# SciQuest_NRF_Mesh.net
KiCad netlist of a schematic drawn in EAGLE
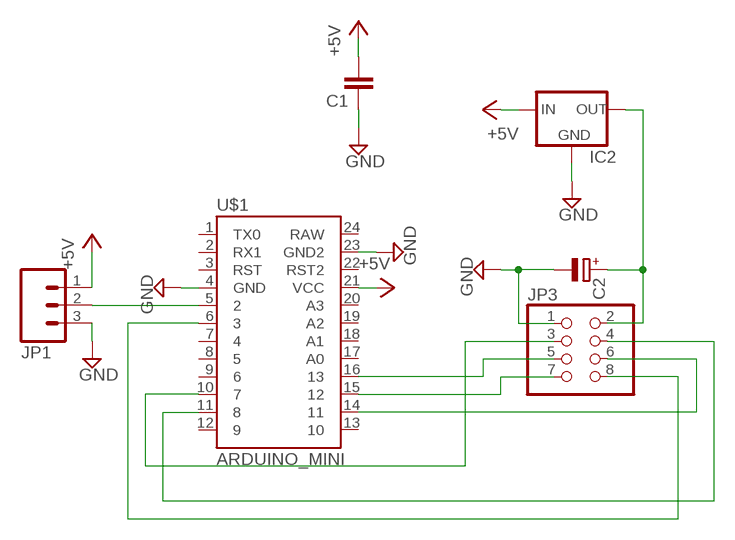
[diagram p0: schematic, sheet 1]

(export (version "E")
  (design (tool "Eeschema 10.0.6"))
  (components
    (comp (ref "C1")
      (value "C-EUC0805K")
      (footprint "eagle-import:C0805K")
      (libsource (lib "eagle-import") (part "C-EUC0805K"))
    )
    (comp (ref "C2")
      (value "CPOL-EUE2-4")
      (footprint "eagle-import:E2-4")
      (libsource (lib "eagle-import") (part "CPOL-EUE2-4"))
    )
    (comp (ref "IC2")
      (value "78LXX")
      (footprint "eagle-import:78LXX")
      (libsource (lib "eagle-import") (part "78LXX"))
    )
    (comp (ref "JP1")
      (value "M03LONGPADS")
      (footprint "eagle-import:1X03_LONGPADS")
      (libsource (lib "eagle-import") (part "M03LONGPADS"))
    )
    (comp (ref "JP3")
      (value "PINHD-2X4")
      (footprint "eagle-import:2X04")
      (libsource (lib "eagle-import") (part "PINHD-2X4"))
    )
    (comp (ref "U$1")
      (value "ARDUINO_MINI")
      (footprint "eagle-import:ARDUINO_MINI")
      (libsource (lib "eagle-import") (part "ARDUINO_MINI"))
    )
  )
  (nets
    (net (code "1") (name "+5V") (class "Default")
      (node (ref "C1") (pin "2") (pinfunction "2_2") (pintype "passive"))
      (node (ref "IC2") (pin "IN") (pinfunction "IN_IN") (pintype "input"))
      (node (ref "JP1") (pin "1") (pinfunction "1_1") (pintype "passive"))
      (node (ref "U$1") (pin "21") (pinfunction "VCC_21") (pintype "bidirectional"))
    )
    (net (code "2") (name "GND") (class "Default")
      (node (ref "C1") (pin "1") (pinfunction "1_1") (pintype "passive"))
      (node (ref "C2") (pin "-") (pinfunction "-_-") (pintype "passive"))
      (node (ref "IC2") (pin "GND") (pinfunction "GND_GND") (pintype "input"))
      (node (ref "JP1") (pin "3") (pinfunction "3_3") (pintype "passive"))
      (node (ref "JP3") (pin "1") (pinfunction "1_1") (pintype "passive"))
      (node (ref "U$1") (pin "23") (pinfunction "GND2_23") (pintype "bidirectional"))
      (node (ref "U$1") (pin "4") (pinfunction "GND_4") (pintype "bidirectional"))
    )
    (net (code "3") (name "Net-(C2-Pad+)") (class "Default")
      (node (ref "C2") (pin "+") (pinfunction "+_+") (pintype "passive"))
      (node (ref "IC2") (pin "OUT") (pinfunction "OUT_OUT") (pintype "passive"))
      (node (ref "JP3") (pin "2") (pinfunction "2_2") (pintype "passive"))
    )
    (net (code "4") (name "Net-(U$1-2)") (class "Default")
      (node (ref "JP1") (pin "2") (pinfunction "2_2") (pintype "passive"))
      (node (ref "U$1") (pin "5") (pinfunction "2_5") (pintype "bidirectional"))
    )
    (net (code "5") (name "Net-(U$1-3)") (class "Default")
      (node (ref "JP3") (pin "8") (pinfunction "8_8") (pintype "passive"))
      (node (ref "U$1") (pin "6") (pinfunction "3_6") (pintype "bidirectional"))
    )
    (net (code "6") (name "Net-(U$1-7)") (class "Default")
      (node (ref "JP3") (pin "3") (pinfunction "3_3") (pintype "passive"))
      (node (ref "U$1") (pin "10") (pinfunction "7_10") (pintype "bidirectional"))
    )
    (net (code "7") (name "Net-(U$1-8)") (class "Default")
      (node (ref "JP3") (pin "4") (pinfunction "4_4") (pintype "passive"))
      (node (ref "U$1") (pin "11") (pinfunction "8_11") (pintype "bidirectional"))
    )
    (net (code "8") (name "Net-(U$1-11)") (class "Default")
      (node (ref "JP3") (pin "6") (pinfunction "6_6") (pintype "passive"))
      (node (ref "U$1") (pin "14") (pinfunction "11_14") (pintype "bidirectional"))
    )
    (net (code "9") (name "Net-(U$1-12)") (class "Default")
      (node (ref "JP3") (pin "7") (pinfunction "7_7") (pintype "passive"))
      (node (ref "U$1") (pin "15") (pinfunction "12_15") (pintype "bidirectional"))
    )
    (net (code "10") (name "Net-(U$1-13)") (class "Default")
      (node (ref "JP3") (pin "5") (pinfunction "5_5") (pintype "passive"))
      (node (ref "U$1") (pin "16") (pinfunction "13_16") (pintype "bidirectional"))
    )
    (net (code "11") (name "unconnected-(U$1-4-Pad7)") (class "Default")
      (node (ref "U$1") (pin "7") (pinfunction "4_7") (pintype "bidirectional"))
    )
    (net (code "12") (name "unconnected-(U$1-5-Pad8)") (class "Default")
      (node (ref "U$1") (pin "8") (pinfunction "5_8") (pintype "bidirectional"))
    )
    (net (code "13") (name "unconnected-(U$1-6-Pad9)") (class "Default")
      (node (ref "U$1") (pin "9") (pinfunction "6_9") (pintype "bidirectional"))
    )
    (net (code "14") (name "unconnected-(U$1-9-Pad12)") (class "Default")
      (node (ref "U$1") (pin "12") (pinfunction "9_12") (pintype "bidirectional"))
    )
    (net (code "15") (name "unconnected-(U$1-10-Pad13)") (class "Default")
      (node (ref "U$1") (pin "13") (pinfunction "10_13") (pintype "bidirectional"))
    )
    (net (code "16") (name "unconnected-(U$1-A0-Pad17)") (class "Default")
      (node (ref "U$1") (pin "17") (pinfunction "A0_17") (pintype "bidirectional"))
    )
    (net (code "17") (name "unconnected-(U$1-A1-Pad18)") (class "Default")
      (node (ref "U$1") (pin "18") (pinfunction "A1_18") (pintype "bidirectional"))
    )
    (net (code "18") (name "unconnected-(U$1-A2-Pad19)") (class "Default")
      (node (ref "U$1") (pin "19") (pinfunction "A2_19") (pintype "bidirectional"))
    )
    (net (code "19") (name "unconnected-(U$1-A3-Pad20)") (class "Default")
      (node (ref "U$1") (pin "20") (pinfunction "A3_20") (pintype "bidirectional"))
    )
    (net (code "20") (name "unconnected-(U$1-RAW-Pad24)") (class "Default")
      (node (ref "U$1") (pin "24") (pinfunction "RAW_24") (pintype "bidirectional"))
    )
    (net (code "21") (name "unconnected-(U$1-RST-Pad3)") (class "Default")
      (node (ref "U$1") (pin "3") (pinfunction "RST_3") (pintype "bidirectional"))
    )
    (net (code "22") (name "unconnected-(U$1-RST2-Pad22)") (class "Default")
      (node (ref "U$1") (pin "22") (pinfunction "RST2_22") (pintype "bidirectional"))
    )
    (net (code "23") (name "unconnected-(U$1-RX1-Pad2)") (class "Default")
      (node (ref "U$1") (pin "2") (pinfunction "RX1_2") (pintype "bidirectional"))
    )
    (net (code "24") (name "unconnected-(U$1-TX0-Pad1)") (class "Default")
      (node (ref "U$1") (pin "1") (pinfunction "TX0_1") (pintype "bidirectional"))
    )
  )
)
